# lpf_60_40.net
KiCad netlist of a schematic drawn in Altium Designer
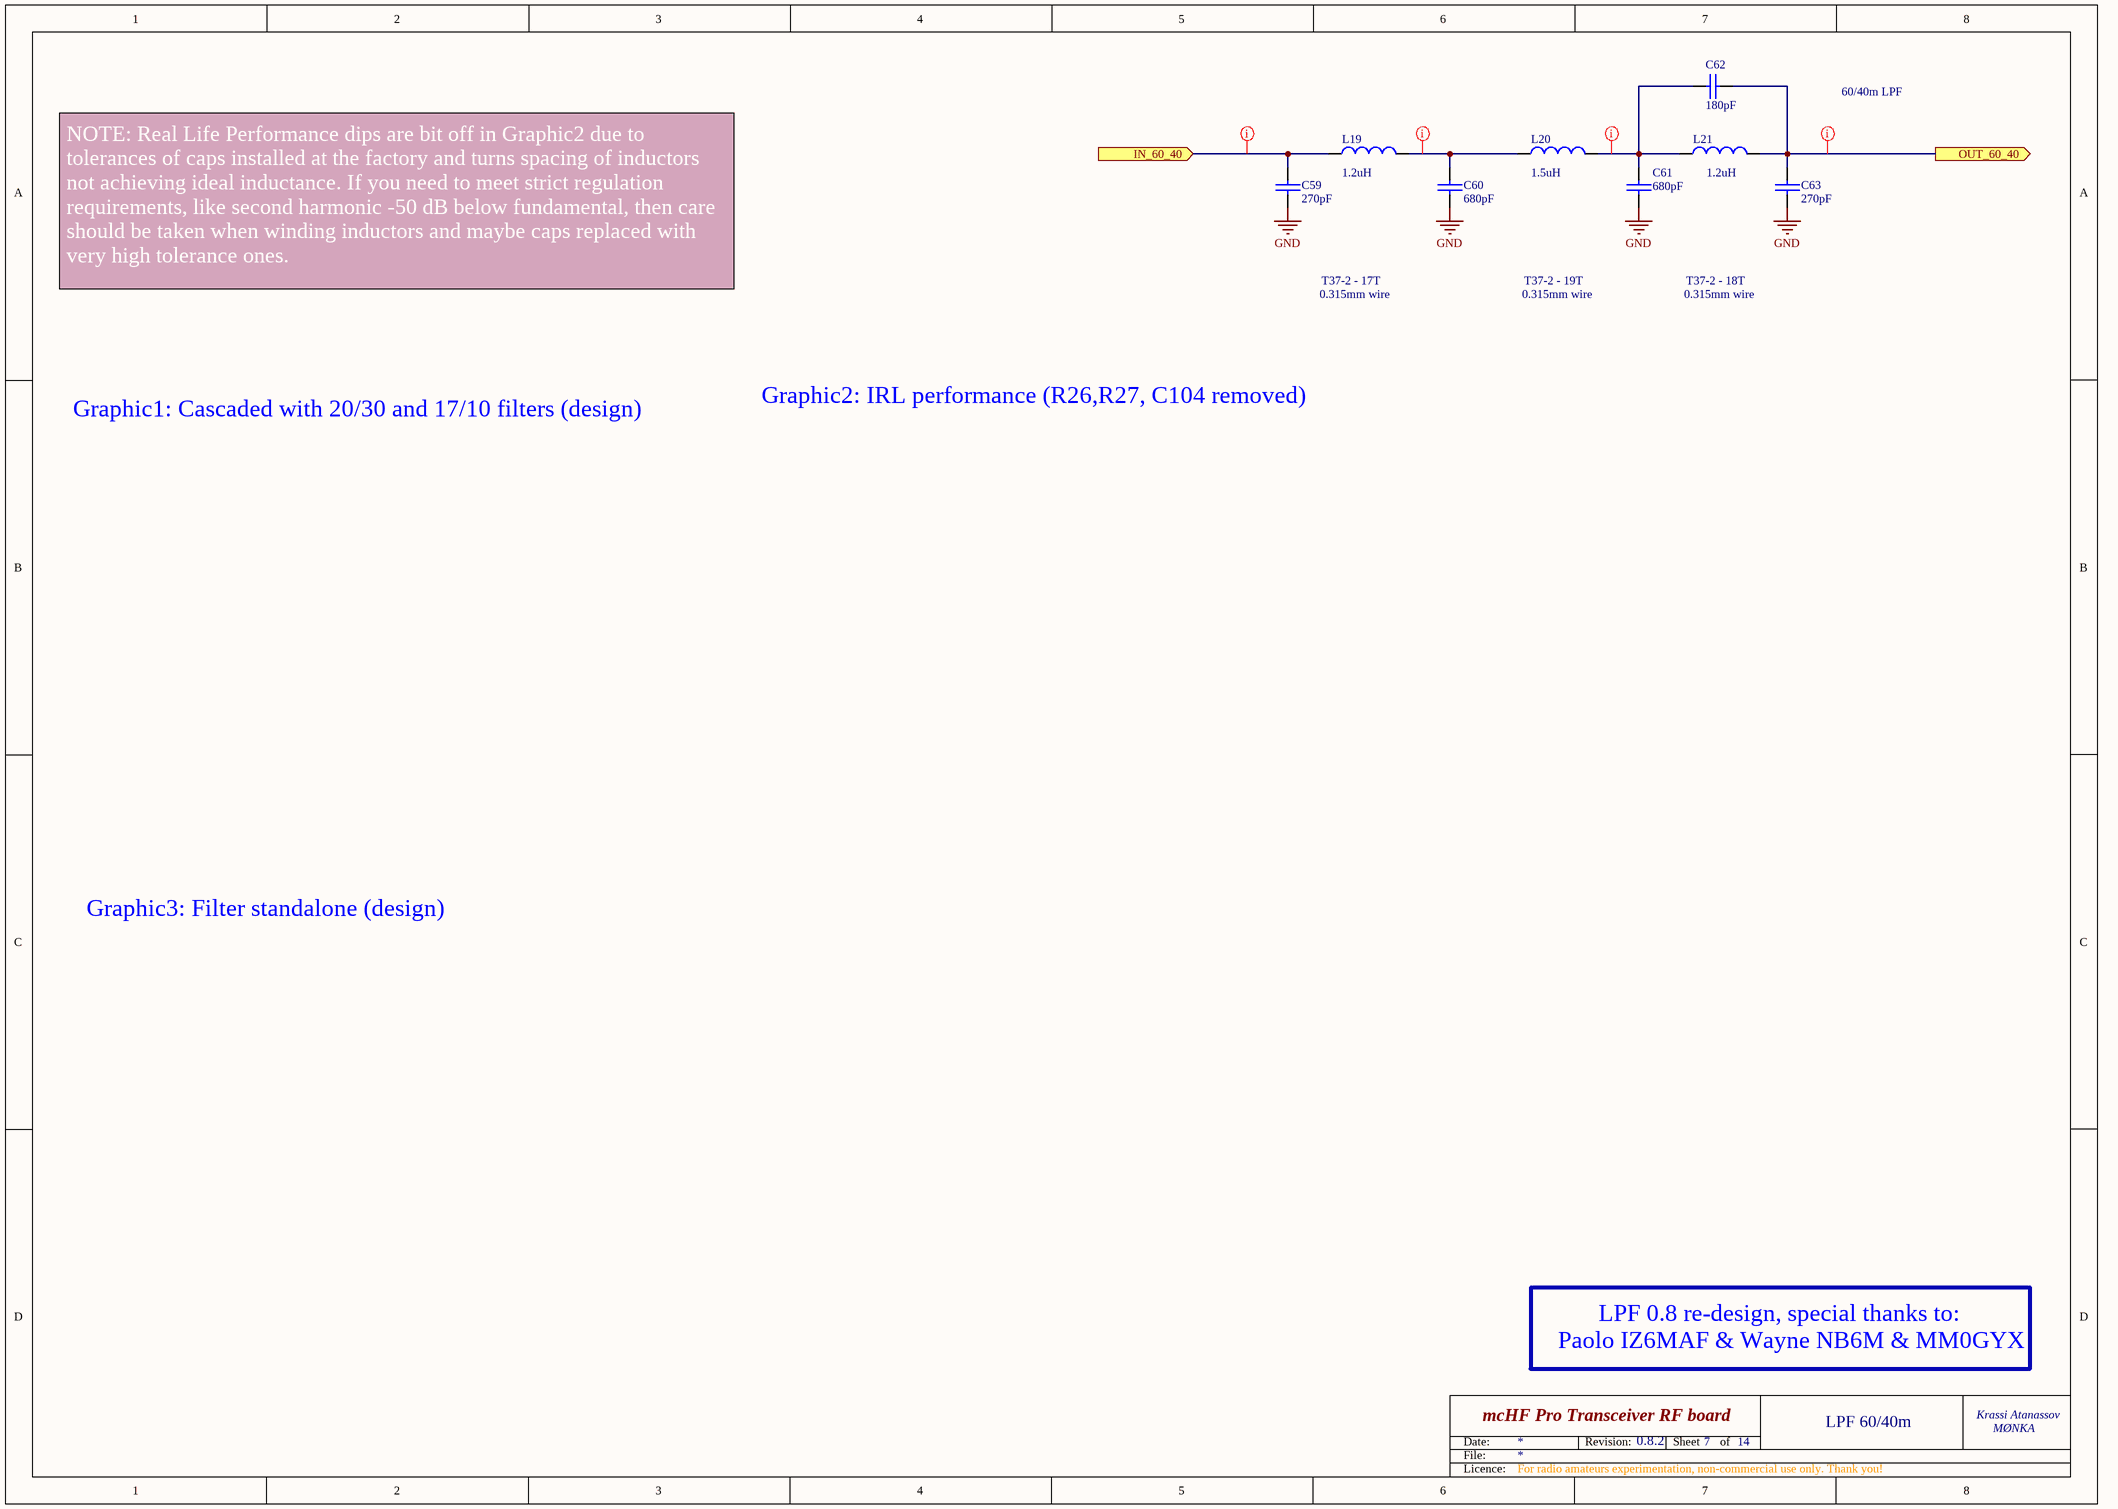
[diagram p0: lpf_60_40.SchDoc]

(export (version "E")
  (design (tool "Eeschema 10.0.6"))
  (components
    (comp (ref "C59")
      (value "270pF")
      (footprint "0805")
      (description "Capacitor")
      (fields (field (name "VOLTAGE") "100V"))
      (libsource (lib "mcHF_rf") (part "CAP"))
    )
    (comp (ref "C60")
      (value "680pF")
      (footprint "0805")
      (description "Capacitor")
      (fields (field (name "VOLTAGE") "100V"))
      (libsource (lib "mcHF_rf") (part "CAP"))
    )
    (comp (ref "C61")
      (value "680pF")
      (footprint "0805")
      (description "Capacitor")
      (fields (field (name "VOLTAGE") "100V"))
      (libsource (lib "mcHF_rf") (part "CAP"))
    )
    (comp (ref "C62")
      (value "180pF")
      (footprint "0805")
      (description "Capacitor")
      (fields (field (name "VOLTAGE") "100V"))
      (libsource (lib "mcHF_rf") (part "CAP"))
    )
    (comp (ref "C63")
      (value "270pF")
      (footprint "0805")
      (description "Capacitor")
      (fields (field (name "VOLTAGE") "100V"))
      (libsource (lib "mcHF_rf") (part "CAP"))
    )
    (comp (ref "L19")
      (value "T37-2")
      (footprint "LPF_IND")
      (description "T37-2 handwound inductor")
      (fields (field (name "INDUCTANCE") "1.2uH"))
      (libsource (lib "mcHF_rf") (part "LPF_IND"))
    )
    (comp (ref "L20")
      (value "T37-2")
      (footprint "LPF_IND")
      (description "T37-2 handwound inductor")
      (fields (field (name "INDUCTANCE") "1.5uH"))
      (libsource (lib "mcHF_rf") (part "LPF_IND"))
    )
    (comp (ref "L21")
      (value "T37-2")
      (footprint "LPF_IND")
      (description "T37-2 handwound inductor")
      (fields (field (name "INDUCTANCE") "1.2uH"))
      (libsource (lib "mcHF_rf") (part "LPF_IND"))
    )
  )
  (nets
    (net (code "1") (name "/IN_60_40") (class "Default")
      (node (ref "C59") (pin "2") (pinfunction "2_2") (pintype "passive"))
      (node (ref "L19") (pin "1") (pinfunction "1_1") (pintype "passive"))
    )
    (net (code "2") (name "/OUT_60_40") (class "Default")
      (node (ref "C62") (pin "1") (pinfunction "1_1") (pintype "passive"))
      (node (ref "C63") (pin "2") (pinfunction "2_2") (pintype "passive"))
      (node (ref "L21") (pin "2") (pinfunction "2_2") (pintype "passive"))
    )
    (net (code "3") (name "GND") (class "Default")
      (node (ref "C59") (pin "1") (pinfunction "1_1") (pintype "passive"))
      (node (ref "C60") (pin "1") (pinfunction "1_1") (pintype "passive"))
      (node (ref "C61") (pin "1") (pinfunction "1_1") (pintype "passive"))
      (node (ref "C63") (pin "1") (pinfunction "1_1") (pintype "passive"))
    )
    (net (code "4") (name "Net-(C60-Pad2)") (class "Default")
      (node (ref "C60") (pin "2") (pinfunction "2_2") (pintype "passive"))
      (node (ref "L19") (pin "2") (pinfunction "2_2") (pintype "passive"))
      (node (ref "L20") (pin "1") (pinfunction "1_1") (pintype "passive"))
    )
    (net (code "5") (name "Net-(C61-Pad2)") (class "Default")
      (node (ref "C61") (pin "2") (pinfunction "2_2") (pintype "passive"))
      (node (ref "C62") (pin "2") (pinfunction "2_2") (pintype "passive"))
      (node (ref "L20") (pin "2") (pinfunction "2_2") (pintype "passive"))
      (node (ref "L21") (pin "1") (pinfunction "1_1") (pintype "passive"))
    )
  )
)
